# Sensors.net
KiCad netlist of a schematic drawn in Altium Designer
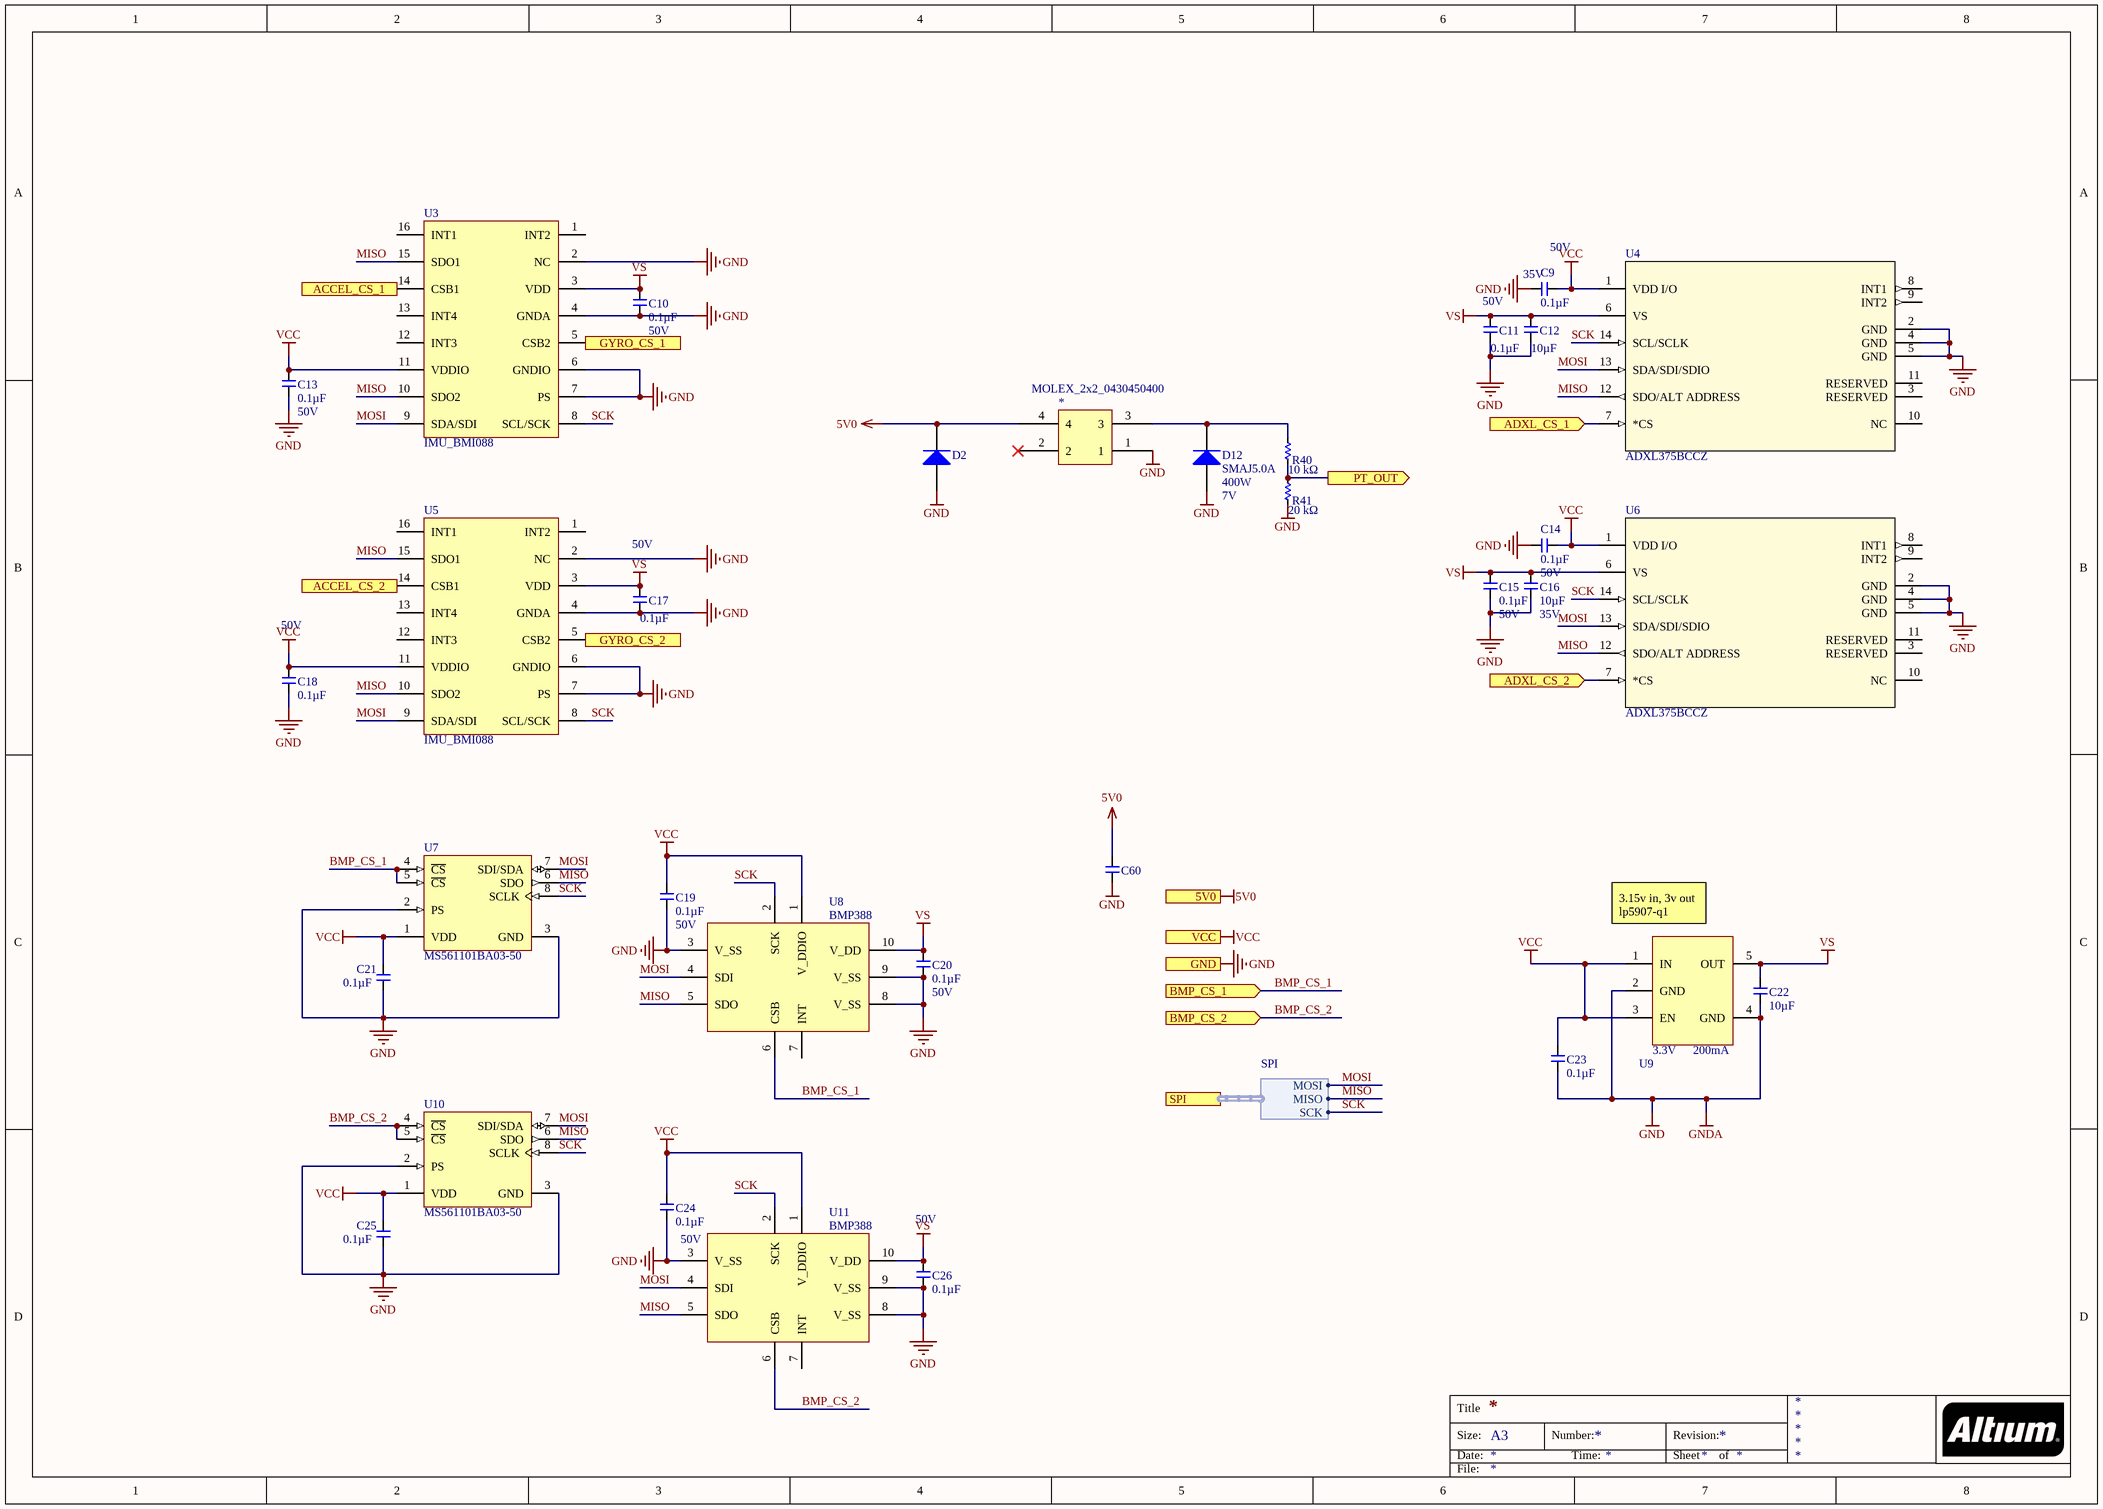
[diagram p0: Sensors.SchDoc]

(export (version "E")
  (design (tool "Eeschema 10.0.6"))
  (components
    (comp (ref "*")
      (value "MOLEX_2x2_0430450400")
      (footprint "MOLEX_2x2_0430450400")
      (description "MICROFIT CONN HEADER R/A 4POS 3MM")
      (libsource (lib "Stanford Student Space Initiative") (part "MOLEX_2x2_0430450400"))
    )
    (comp (ref "C9")
      (value "490-1519-1-ND")
      (footprint "C0603")
      (description "CAP CER 0603 0.1µF X7R 50V 10%")
      (fields
        (field (name "CAPACITANCE (SHORTHAND)") "0.1µF")
        (field (name "MANUFACTURER") "Murata Electronics North America")
        (field (name "RATED VOLTAGE") "50V")
      )
      (libsource (lib "Stanford Student Space Initiative") (part "__template_cap"))
    )
    (comp (ref "C10")
      (value "490-1519-1-ND")
      (footprint "C0603")
      (description "CAP CER 0603 0.1µF X7R 50V 10%")
      (fields
        (field (name "CAPACITANCE (SHORTHAND)") "0.1µF")
        (field (name "MANUFACTURER") "Murata Electronics North America")
        (field (name "RATED VOLTAGE") "50V")
      )
      (libsource (lib "Stanford Student Space Initiative") (part "__template_cap"))
    )
    (comp (ref "C11")
      (value "490-1519-1-ND")
      (footprint "C0603")
      (description "CAP CER 0603 0.1µF X7R 50V 10%")
      (fields
        (field (name "CAPACITANCE (SHORTHAND)") "0.1µF")
        (field (name "MANUFACTURER") "Murata Electronics North America")
        (field (name "RATED VOLTAGE") "50V")
      )
      (libsource (lib "Stanford Student Space Initiative") (part "__template_cap"))
    )
    (comp (ref "C12")
      (value "490-13248-1-ND")
      (footprint "C0603")
      (description "CAP CER 10UF 35V X5R 0603 20%")
      (fields
        (field (name "CAPACITANCE (SHORTHAND)") "10µF")
        (field (name "MANUFACTURER") "Murata Electronics North America")
        (field (name "RATED VOLTAGE") "35V")
      )
      (libsource (lib "Stanford Student Space Initiative") (part "__template_cap"))
    )
    (comp (ref "C13")
      (value "490-1519-1-ND")
      (footprint "C0603")
      (description "CAP CER 0603 0.1µF X7R 50V 10%")
      (fields
        (field (name "CAPACITANCE (SHORTHAND)") "0.1µF")
        (field (name "MANUFACTURER") "Murata Electronics North America")
        (field (name "RATED VOLTAGE") "50V")
      )
      (libsource (lib "Stanford Student Space Initiative") (part "__template_cap"))
    )
    (comp (ref "C14")
      (value "490-1519-1-ND")
      (footprint "C0603")
      (description "CAP CER 0603 0.1µF X7R 50V 10%")
      (fields
        (field (name "CAPACITANCE (SHORTHAND)") "0.1µF")
        (field (name "MANUFACTURER") "Murata Electronics North America")
        (field (name "RATED VOLTAGE") "50V")
      )
      (libsource (lib "Stanford Student Space Initiative") (part "__template_cap"))
    )
    (comp (ref "C15")
      (value "490-1519-1-ND")
      (footprint "C0603")
      (description "CAP CER 0603 0.1µF X7R 50V 10%")
      (fields
        (field (name "CAPACITANCE (SHORTHAND)") "0.1µF")
        (field (name "MANUFACTURER") "Murata Electronics North America")
        (field (name "RATED VOLTAGE") "50V")
      )
      (libsource (lib "Stanford Student Space Initiative") (part "__template_cap"))
    )
    (comp (ref "C16")
      (value "490-13248-1-ND")
      (footprint "C0603")
      (description "CAP CER 10UF 35V X5R 0603 20%")
      (fields
        (field (name "CAPACITANCE (SHORTHAND)") "10µF")
        (field (name "MANUFACTURER") "Murata Electronics North America")
        (field (name "RATED VOLTAGE") "35V")
      )
      (libsource (lib "Stanford Student Space Initiative") (part "__template_cap"))
    )
    (comp (ref "C17")
      (value "490-1519-1-ND")
      (footprint "C0603")
      (description "CAP CER 0603 0.1µF X7R 50V 10%")
      (fields
        (field (name "CAPACITANCE (SHORTHAND)") "0.1µF")
        (field (name "MANUFACTURER") "Murata Electronics North America")
        (field (name "RATED VOLTAGE") "50V")
      )
      (libsource (lib "Stanford Student Space Initiative") (part "__template_cap"))
    )
    (comp (ref "C18")
      (value "490-1519-1-ND")
      (footprint "C0603")
      (description "CAP CER 0603 0.1µF X7R 50V 10%")
      (fields
        (field (name "CAPACITANCE (SHORTHAND)") "0.1µF")
        (field (name "MANUFACTURER") "Murata Electronics North America")
        (field (name "RATED VOLTAGE") "50V")
      )
      (libsource (lib "Stanford Student Space Initiative") (part "__template_cap"))
    )
    (comp (ref "C19")
      (value "490-1519-1-ND")
      (footprint "C0603")
      (description "CAP CER 0603 0.1µF X7R 50V 10%")
      (fields
        (field (name "CAPACITANCE (SHORTHAND)") "0.1µF")
        (field (name "MANUFACTURER") "Murata Electronics North America")
        (field (name "RATED VOLTAGE") "50V")
      )
      (libsource (lib "Stanford Student Space Initiative") (part "__template_cap"))
    )
    (comp (ref "C20")
      (value "490-1519-1-ND")
      (footprint "C0603")
      (description "CAP CER 0603 0.1µF X7R 50V 10%")
      (fields
        (field (name "CAPACITANCE (SHORTHAND)") "0.1µF")
        (field (name "MANUFACTURER") "Murata Electronics North America")
        (field (name "RATED VOLTAGE") "50V")
      )
      (libsource (lib "Stanford Student Space Initiative") (part "__template_cap"))
    )
    (comp (ref "C21")
      (value "490-1519-1-ND")
      (footprint "C0603")
      (description "CAP CER 0603 0.1µF X7R 50V 10%")
      (fields
        (field (name "MANUFACTURER") "Murata Electronics North America")
        (field (name "CAPACITANCE (SHORTHAND)") "0.1µF")
      )
      (libsource (lib "Stanford Student Space Initiative") (part "__template_cap"))
    )
    (comp (ref "C22")
      (value "490-13248-1-ND")
      (footprint "C0603")
      (description "CAP CER 10UF 35V X5R 0603 20%")
      (fields
        (field (name "CAPACITANCE (SHORTHAND)") "10µF")
        (field (name "MANUFACTURER") "Murata Electronics North America")
      )
      (libsource (lib "Stanford Student Space Initiative") (part "__template_cap"))
    )
    (comp (ref "C23")
      (value "490-1519-1-ND")
      (footprint "C0603")
      (description "CAP CER 0603 0.1µF X7R 50V 10%")
      (fields
        (field (name "CAPACITANCE (SHORTHAND)") "0.1µF")
        (field (name "MANUFACTURER") "Murata Electronics North America")
      )
      (libsource (lib "Stanford Student Space Initiative") (part "__template_cap"))
    )
    (comp (ref "C24")
      (value "490-1519-1-ND")
      (footprint "C0603")
      (description "CAP CER 0603 0.1µF X7R 50V 10%")
      (fields
        (field (name "CAPACITANCE (SHORTHAND)") "0.1µF")
        (field (name "MANUFACTURER") "Murata Electronics North America")
        (field (name "RATED VOLTAGE") "50V")
      )
      (libsource (lib "Stanford Student Space Initiative") (part "__template_cap"))
    )
    (comp (ref "C25")
      (value "490-1519-1-ND")
      (footprint "C0603")
      (description "CAP CER 0603 0.1µF X7R 50V 10%")
      (fields
        (field (name "MANUFACTURER") "Murata Electronics North America")
        (field (name "CAPACITANCE (SHORTHAND)") "0.1µF")
      )
      (libsource (lib "Stanford Student Space Initiative") (part "__template_cap"))
    )
    (comp (ref "C26")
      (value "490-1519-1-ND")
      (footprint "C0603")
      (description "CAP CER 0603 0.1µF X7R 50V 10%")
      (fields
        (field (name "CAPACITANCE (SHORTHAND)") "0.1µF")
        (field (name "MANUFACTURER") "Murata Electronics North America")
        (field (name "RATED VOLTAGE") "50V")
      )
      (libsource (lib "Stanford Student Space Initiative") (part "__template_cap"))
    )
    (comp (ref "C60")
      (value "490-1519-1-ND")
      (footprint "C0603")
      (description "CAP CER 0603 0.1µF X7R 50V 10%")
      (fields (field (name "MANUFACTURER") "Murata Electronics North America"))
      (libsource (lib "Stanford Student Space Initiative") (part "__template_cap"))
    )
    (comp (ref "D2")
      (value "SMAJ5.0A")
      (footprint "BOUR-SMA-2_V")
      (description "BOURNS - SMAJ5.0A - TVS Diode, SMAJ Series, Unidirectional, 5 V, 9.2 V, DO-214AC (SMA), 2 Pins")
      (libsource (lib "Stanford Student Space Initiative") (part "D-AK-2"))
    )
    (comp (ref "D12")
      (value "SMAJ5.0A")
      (footprint "BOUR-SMA-2_V")
      (description "BOURNS - SMAJ5.0A - TVS Diode, SMAJ Series, Unidirectional, 5 V, 9.2 V, DO-214AC (SMA), 2 Pins")
      (fields (field (name "MAX POWER DISSIPATION") "400W") (field (name "BREAKDOWN VOLTAGE") "7V"))
      (libsource (lib "Stanford Student Space Initiative") (part "D-AK-2"))
    )
    (comp (ref "R40")
      (value "311-10.0KHRCT-ND")
      (footprint "R0603")
      (description "RES SMD 10K OHM 1% 1/10W 0603")
      (fields
        (field (name "MANUFACTURER") "Yageo")
        (field (name "MANUFACTURER PART NUMBER") "RC0603FR-0710KL")
        (field (name "RESISTANCE") "10 kΩ")
      )
      (libsource (lib "Stanford Student Space Initiative") (part "__template_resistor"))
    )
    (comp (ref "R41")
      (value "311-20.0KHRCT-ND")
      (footprint "R0603")
      (description "RES SMD 20K OHM 1% 1/10W 0603")
      (fields
        (field (name "MANUFACTURER PART NUMBER") "RC0603FR-0720KL")
        (field (name "MANUFACTURER") "Yageo")
        (field (name "RESISTANCE") "20 kΩ")
      )
      (libsource (lib "Stanford Student Space Initiative") (part "__template_resistor"))
    )
    (comp (ref "U3")
      (value "IMU_BMI088")
      (footprint "BMI088")
      (description "Bosch BMI088")
      (libsource (lib "Stanford Student Space Initiative") (part "IMU_BMI088"))
    )
    (comp (ref "U4")
      (value "ADXL375BCCZ")
      (footprint "LGA_CC-14-1")
      (description "200G Accelcerometer")
      (fields
        (field (name "MANUFACTURER") "Analog Devices")
        (field (name "MANUFACTURER PART NUMBER") "ADXL375BCCZ-RL7")
      )
      (libsource (lib "Stanford Student Space Initiative") (part "ADXL375BCCZ"))
    )
    (comp (ref "U5")
      (value "IMU_BMI088")
      (footprint "BMI088")
      (description "Bosch BMI088")
      (libsource (lib "Stanford Student Space Initiative") (part "IMU_BMI088"))
    )
    (comp (ref "U6")
      (value "ADXL375BCCZ")
      (footprint "LGA_CC-14-1")
      (description "200G Accelcerometer")
      (fields
        (field (name "MANUFACTURER") "Analog Devices")
        (field (name "MANUFACTURER PART NUMBER") "ADXL375BCCZ-RL7")
      )
      (libsource (lib "Stanford Student Space Initiative") (part "ADXL375BCCZ"))
    )
    (comp (ref "U7")
      (value "MS561101BA03-50")
      (footprint "MSI-MS561101BA03-50-8_V")
      (description "Pressure Sensor 1.44V to 3.6V 0.01bar to 1.2bar Absolute 8-Pin QFN T/R")
      (libsource (lib "Stanford Student Space Initiative") (part "MSI-MS561101BA03-50-8"))
    )
    (comp (ref "U8")
      (value "BMP388")
      (footprint "8 pin LGA")
      (description "SENSOR PRESSURE ABS")
      (fields (field (name "MANUFACTURER") "Bosch Sensortec"))
      (libsource (lib "Stanford Student Space Initiative") (part "BMP388"))
    )
    (comp (ref "U9")
      (value "LDO_TLV70033QDDCRQ1")
      (footprint "5SOT23")
      (description "IC REG LDO 3.3V .2A SOT23-5")
      (fields
        (field (name "MANUFACTURER") "Texas Instruments")
        (field (name "MANUFACTURER PART NUMBER") "TLV70033QDDCRQ1")
        (field (name "VOLTAGE - OUTPUT") "3.3V")
        (field (name "CURRENT - OUTPUT") "200mA")
      )
      (libsource (lib "Stanford Student Space Initiative") (part "LDO_TLV70033QDDCRQ1"))
    )
    (comp (ref "U10")
      (value "MS561101BA03-50")
      (footprint "MSI-MS561101BA03-50-8_V")
      (description "Pressure Sensor 1.44V to 3.6V 0.01bar to 1.2bar Absolute 8-Pin QFN T/R")
      (libsource (lib "Stanford Student Space Initiative") (part "MSI-MS561101BA03-50-8"))
    )
    (comp (ref "U11")
      (value "BMP388")
      (footprint "8 pin LGA")
      (description "SENSOR PRESSURE ABS")
      (fields (field (name "MANUFACTURER") "Bosch Sensortec"))
      (libsource (lib "Stanford Student Space Initiative") (part "BMP388"))
    )
  )
  (nets
    (net (code "2") (name "/ACCEL_CS_1") (class "Default")
      (node (ref "U3") (pin "14") (pinfunction "CSB1_14") (pintype "passive"))
    )
    (net (code "3") (name "/ACCEL_CS_2") (class "Default")
      (node (ref "U5") (pin "14") (pinfunction "CSB1_14") (pintype "passive"))
    )
    (net (code "4") (name "/ADXL_CS_1") (class "Default")
      (node (ref "U4") (pin "7") (pinfunction "*CS_7") (pintype "input"))
    )
    (net (code "5") (name "/ADXL_CS_2") (class "Default")
      (node (ref "U6") (pin "7") (pinfunction "*CS_7") (pintype "input"))
    )
    (net (code "6") (name "/BMP_CS_1") (class "Default")
      (node (ref "U7") (pin "4") (pinfunction "~{CS}_4") (pintype "input"))
      (node (ref "U7") (pin "5") (pinfunction "~{CS}_5") (pintype "input"))
      (node (ref "U8") (pin "6") (pinfunction "CSB_6") (pintype "passive"))
    )
    (net (code "7") (name "/BMP_CS_2") (class "Default")
      (node (ref "U10") (pin "4") (pinfunction "~{CS}_4") (pintype "input"))
      (node (ref "U10") (pin "5") (pinfunction "~{CS}_5") (pintype "input"))
      (node (ref "U11") (pin "6") (pinfunction "CSB_6") (pintype "passive"))
    )
    (net (code "8") (name "/GYRO_CS_1") (class "Default")
      (node (ref "U3") (pin "5") (pinfunction "CSB2_5") (pintype "passive"))
    )
    (net (code "9") (name "/GYRO_CS_2") (class "Default")
      (node (ref "U5") (pin "5") (pinfunction "CSB2_5") (pintype "passive"))
    )
    (net (code "10") (name "/MISO") (class "Default")
      (node (ref "U10") (pin "6") (pinfunction "SDO_6") (pintype "output"))
      (node (ref "U11") (pin "5") (pinfunction "SDO_5") (pintype "passive"))
      (node (ref "U3") (pin "10") (pinfunction "SDO2_10") (pintype "passive"))
      (node (ref "U3") (pin "15") (pinfunction "SDO1_15") (pintype "passive"))
      (node (ref "U4") (pin "12") (pinfunction "SDO/ALT_ADDRESS_12") (pintype "output"))
      (node (ref "U5") (pin "10") (pinfunction "SDO2_10") (pintype "passive"))
      (node (ref "U5") (pin "15") (pinfunction "SDO1_15") (pintype "passive"))
      (node (ref "U6") (pin "12") (pinfunction "SDO/ALT_ADDRESS_12") (pintype "output"))
      (node (ref "U7") (pin "6") (pinfunction "SDO_6") (pintype "output"))
      (node (ref "U8") (pin "5") (pinfunction "SDO_5") (pintype "passive"))
    )
    (net (code "11") (name "/MOSI") (class "Default")
      (node (ref "U10") (pin "7") (pinfunction "SDI/SDA_7") (pintype "bidirectional"))
      (node (ref "U11") (pin "4") (pinfunction "SDI_4") (pintype "passive"))
      (node (ref "U3") (pin "9") (pinfunction "SDA/SDI_9") (pintype "passive"))
      (node (ref "U4") (pin "13") (pinfunction "SDA/SDI/SDIO_13") (pintype "input"))
      (node (ref "U5") (pin "9") (pinfunction "SDA/SDI_9") (pintype "passive"))
      (node (ref "U6") (pin "13") (pinfunction "SDA/SDI/SDIO_13") (pintype "input"))
      (node (ref "U7") (pin "7") (pinfunction "SDI/SDA_7") (pintype "bidirectional"))
      (node (ref "U8") (pin "4") (pinfunction "SDI_4") (pintype "passive"))
    )
    (net (code "12") (name "/PT_OUT") (class "Default")
      (node (ref "R40") (pin "1") (pinfunction "1_1") (pintype "passive"))
      (node (ref "R41") (pin "2") (pinfunction "2_2") (pintype "passive"))
    )
    (net (code "13") (name "/SCK") (class "Default")
      (node (ref "U10") (pin "8") (pinfunction "SCLK_8") (pintype "input"))
      (node (ref "U11") (pin "2") (pinfunction "SCK_2") (pintype "passive"))
      (node (ref "U3") (pin "8") (pinfunction "SCL/SCK_8") (pintype "passive"))
      (node (ref "U4") (pin "14") (pinfunction "SCL/SCLK_14") (pintype "input"))
      (node (ref "U5") (pin "8") (pinfunction "SCL/SCK_8") (pintype "passive"))
      (node (ref "U6") (pin "14") (pinfunction "SCL/SCLK_14") (pintype "input"))
      (node (ref "U7") (pin "8") (pinfunction "SCLK_8") (pintype "input"))
      (node (ref "U8") (pin "2") (pinfunction "SCK_2") (pintype "passive"))
    )
    (net (code "15") (name "5V0") (class "Default")
      (node (ref "*") (pin "4") (pinfunction "4_4") (pintype "passive"))
      (node (ref "C60") (pin "1") (pintype "passive"))
      (node (ref "D2") (pin "2") (pinfunction "K_2") (pintype "passive"))
    )
    (net (code "16") (name "GND") (class "Default")
      (node (ref "*") (pin "1") (pinfunction "1_1") (pintype "passive"))
      (node (ref "C10") (pin "2") (pintype "passive"))
      (node (ref "C11") (pin "1") (pintype "passive"))
      (node (ref "C12") (pin "2") (pintype "passive"))
      (node (ref "C13") (pin "2") (pintype "passive"))
      (node (ref "C14") (pin "2") (pintype "passive"))
      (node (ref "C15") (pin "1") (pintype "passive"))
      (node (ref "C16") (pin "2") (pintype "passive"))
      (node (ref "C17") (pin "2") (pintype "passive"))
      (node (ref "C18") (pin "2") (pintype "passive"))
      (node (ref "C19") (pin "2") (pintype "passive"))
      (node (ref "C20") (pin "2") (pintype "passive"))
      (node (ref "C21") (pin "2") (pintype "passive"))
      (node (ref "C22") (pin "2") (pintype "passive"))
      (node (ref "C23") (pin "2") (pintype "passive"))
      (node (ref "C24") (pin "2") (pintype "passive"))
      (node (ref "C25") (pin "2") (pintype "passive"))
      (node (ref "C26") (pin "2") (pintype "passive"))
      (node (ref "C60") (pin "2") (pintype "passive"))
      (node (ref "C9") (pin "2") (pintype "passive"))
      (node (ref "D12") (pin "1") (pinfunction "A_1") (pintype "passive"))
      (node (ref "D2") (pin "1") (pinfunction "A_1") (pintype "passive"))
      (node (ref "R41") (pin "1") (pinfunction "1_1") (pintype "passive"))
      (node (ref "U10") (pin "2") (pinfunction "PS_2") (pintype "input"))
      (node (ref "U10") (pin "3") (pinfunction "GND_3") (pintype "power_in"))
      (node (ref "U11") (pin "3") (pinfunction "V_SS_3") (pintype "passive"))
      (node (ref "U11") (pin "8") (pinfunction "V_SS_8") (pintype "passive"))
      (node (ref "U11") (pin "9") (pinfunction "V_SS_9") (pintype "passive"))
      (node (ref "U3") (pin "2") (pinfunction "NC_2") (pintype "passive"))
      (node (ref "U3") (pin "4") (pinfunction "GNDA_4") (pintype "passive"))
      (node (ref "U3") (pin "6") (pinfunction "GNDIO_6") (pintype "passive"))
      (node (ref "U3") (pin "7") (pinfunction "PS_7") (pintype "passive"))
      (node (ref "U4") (pin "2") (pinfunction "GND_2") (pintype "power_in"))
      (node (ref "U4") (pin "4") (pinfunction "GND_4") (pintype "power_in"))
      (node (ref "U4") (pin "5") (pinfunction "GND_5") (pintype "power_in"))
      (node (ref "U5") (pin "2") (pinfunction "NC_2") (pintype "passive"))
      (node (ref "U5") (pin "4") (pinfunction "GNDA_4") (pintype "passive"))
      (node (ref "U5") (pin "6") (pinfunction "GNDIO_6") (pintype "passive"))
      (node (ref "U5") (pin "7") (pinfunction "PS_7") (pintype "passive"))
      (node (ref "U6") (pin "2") (pinfunction "GND_2") (pintype "power_in"))
      (node (ref "U6") (pin "4") (pinfunction "GND_4") (pintype "power_in"))
      (node (ref "U6") (pin "5") (pinfunction "GND_5") (pintype "power_in"))
      (node (ref "U7") (pin "2") (pinfunction "PS_2") (pintype "input"))
      (node (ref "U7") (pin "3") (pinfunction "GND_3") (pintype "power_in"))
      (node (ref "U8") (pin "3") (pinfunction "V_SS_3") (pintype "passive"))
      (node (ref "U8") (pin "8") (pinfunction "V_SS_8") (pintype "passive"))
      (node (ref "U8") (pin "9") (pinfunction "V_SS_9") (pintype "passive"))
      (node (ref "U9") (pin "2") (pinfunction "GND_2") (pintype "passive"))
      (node (ref "U9") (pin "4") (pinfunction "GND_4") (pintype "passive"))
    )
    (net (code "17") (name "Net-(D12-K)") (class "Default")
      (node (ref "*") (pin "3") (pinfunction "3_3") (pintype "passive"))
      (node (ref "D12") (pin "2") (pinfunction "K_2") (pintype "passive"))
      (node (ref "R40") (pin "2") (pinfunction "2_2") (pintype "passive"))
    )
    (net (code "18") (name "VCC") (class "Default")
      (node (ref "C13") (pin "1") (pintype "passive"))
      (node (ref "C14") (pin "1") (pintype "passive"))
      (node (ref "C18") (pin "1") (pintype "passive"))
      (node (ref "C19") (pin "1") (pintype "passive"))
      (node (ref "C21") (pin "1") (pintype "passive"))
      (node (ref "C23") (pin "1") (pintype "passive"))
      (node (ref "C24") (pin "1") (pintype "passive"))
      (node (ref "C25") (pin "1") (pintype "passive"))
      (node (ref "C9") (pin "1") (pintype "passive"))
      (node (ref "U10") (pin "1") (pinfunction "VDD_1") (pintype "power_in"))
      (node (ref "U11") (pin "1") (pinfunction "V_DDIO_1") (pintype "passive"))
      (node (ref "U3") (pin "11") (pinfunction "VDDIO_11") (pintype "passive"))
      (node (ref "U4") (pin "1") (pinfunction "VDD_I/O_1") (pintype "power_in"))
      (node (ref "U5") (pin "11") (pinfunction "VDDIO_11") (pintype "passive"))
      (node (ref "U6") (pin "1") (pinfunction "VDD_I/O_1") (pintype "power_in"))
      (node (ref "U7") (pin "1") (pinfunction "VDD_1") (pintype "power_in"))
      (node (ref "U8") (pin "1") (pinfunction "V_DDIO_1") (pintype "passive"))
      (node (ref "U9") (pin "1") (pinfunction "IN_1") (pintype "passive"))
      (node (ref "U9") (pin "3") (pinfunction "EN_3") (pintype "passive"))
    )
    (net (code "19") (name "VS") (class "Default")
      (node (ref "C10") (pin "1") (pintype "passive"))
      (node (ref "C11") (pin "2") (pintype "passive"))
      (node (ref "C12") (pin "1") (pintype "passive"))
      (node (ref "C15") (pin "2") (pintype "passive"))
      (node (ref "C16") (pin "1") (pintype "passive"))
      (node (ref "C17") (pin "1") (pintype "passive"))
      (node (ref "C20") (pin "1") (pintype "passive"))
      (node (ref "C22") (pin "1") (pintype "passive"))
      (node (ref "C26") (pin "1") (pintype "passive"))
      (node (ref "U11") (pin "10") (pinfunction "V_DD_10") (pintype "passive"))
      (node (ref "U3") (pin "3") (pinfunction "VDD_3") (pintype "passive"))
      (node (ref "U4") (pin "6") (pinfunction "VS_6") (pintype "power_in"))
      (node (ref "U5") (pin "3") (pinfunction "VDD_3") (pintype "passive"))
      (node (ref "U6") (pin "6") (pinfunction "VS_6") (pintype "power_in"))
      (node (ref "U8") (pin "10") (pinfunction "V_DD_10") (pintype "passive"))
      (node (ref "U9") (pin "5") (pinfunction "OUT_5") (pintype "passive"))
    )
    (net (code "20") (name "unconnected-(*-Pad2)") (class "Default")
      (node (ref "*") (pin "2") (pinfunction "2_2") (pintype "passive+no_connect"))
    )
    (net (code "21") (name "unconnected-(U3-INT1-Pad16)") (class "Default")
      (node (ref "U3") (pin "16") (pinfunction "INT1_16") (pintype "passive"))
    )
    (net (code "22") (name "unconnected-(U3-INT2-Pad1)") (class "Default")
      (node (ref "U3") (pin "1") (pinfunction "INT2_1") (pintype "passive"))
    )
    (net (code "23") (name "unconnected-(U3-INT3-Pad12)") (class "Default")
      (node (ref "U3") (pin "12") (pinfunction "INT3_12") (pintype "passive"))
    )
    (net (code "24") (name "unconnected-(U3-INT4-Pad13)") (class "Default")
      (node (ref "U3") (pin "13") (pinfunction "INT4_13") (pintype "passive"))
    )
    (net (code "25") (name "unconnected-(U4-INT1-Pad8)") (class "Default")
      (node (ref "U4") (pin "8") (pinfunction "INT1_8") (pintype "output"))
    )
    (net (code "26") (name "unconnected-(U4-INT2-Pad9)") (class "Default")
      (node (ref "U4") (pin "9") (pinfunction "INT2_9") (pintype "output"))
    )
    (net (code "27") (name "unconnected-(U4-NC-Pad10)") (class "Default")
      (node (ref "U4") (pin "10") (pinfunction "NC_10") (pintype "passive"))
    )
    (net (code "28") (name "unconnected-(U4-RESERVED-Pad3)") (class "Default")
      (node (ref "U4") (pin "3") (pinfunction "RESERVED_3") (pintype "passive"))
    )
    (net (code "29") (name "unconnected-(U4-RESERVED-Pad11)") (class "Default")
      (node (ref "U4") (pin "11") (pinfunction "RESERVED_11") (pintype "passive"))
    )
    (net (code "30") (name "unconnected-(U5-INT1-Pad16)") (class "Default")
      (node (ref "U5") (pin "16") (pinfunction "INT1_16") (pintype "passive"))
    )
    (net (code "31") (name "unconnected-(U5-INT2-Pad1)") (class "Default")
      (node (ref "U5") (pin "1") (pinfunction "INT2_1") (pintype "passive"))
    )
    (net (code "32") (name "unconnected-(U5-INT3-Pad12)") (class "Default")
      (node (ref "U5") (pin "12") (pinfunction "INT3_12") (pintype "passive"))
    )
    (net (code "33") (name "unconnected-(U5-INT4-Pad13)") (class "Default")
      (node (ref "U5") (pin "13") (pinfunction "INT4_13") (pintype "passive"))
    )
    (net (code "34") (name "unconnected-(U6-INT1-Pad8)") (class "Default")
      (node (ref "U6") (pin "8") (pinfunction "INT1_8") (pintype "output"))
    )
    (net (code "35") (name "unconnected-(U6-INT2-Pad9)") (class "Default")
      (node (ref "U6") (pin "9") (pinfunction "INT2_9") (pintype "output"))
    )
    (net (code "36") (name "unconnected-(U6-NC-Pad10)") (class "Default")
      (node (ref "U6") (pin "10") (pinfunction "NC_10") (pintype "passive"))
    )
    (net (code "37") (name "unconnected-(U6-RESERVED-Pad3)") (class "Default")
      (node (ref "U6") (pin "3") (pinfunction "RESERVED_3") (pintype "passive"))
    )
    (net (code "38") (name "unconnected-(U6-RESERVED-Pad11)") (class "Default")
      (node (ref "U6") (pin "11") (pinfunction "RESERVED_11") (pintype "passive"))
    )
    (net (code "39") (name "unconnected-(U8-INT-Pad7)") (class "Default")
      (node (ref "U8") (pin "7") (pinfunction "INT_7") (pintype "passive"))
    )
    (net (code "40") (name "unconnected-(U11-INT-Pad7)") (class "Default")
      (node (ref "U11") (pin "7") (pinfunction "INT_7") (pintype "passive"))
    )
  )
)
